# TopSide.net
KiCad netlist of a schematic drawn in Altium Designer
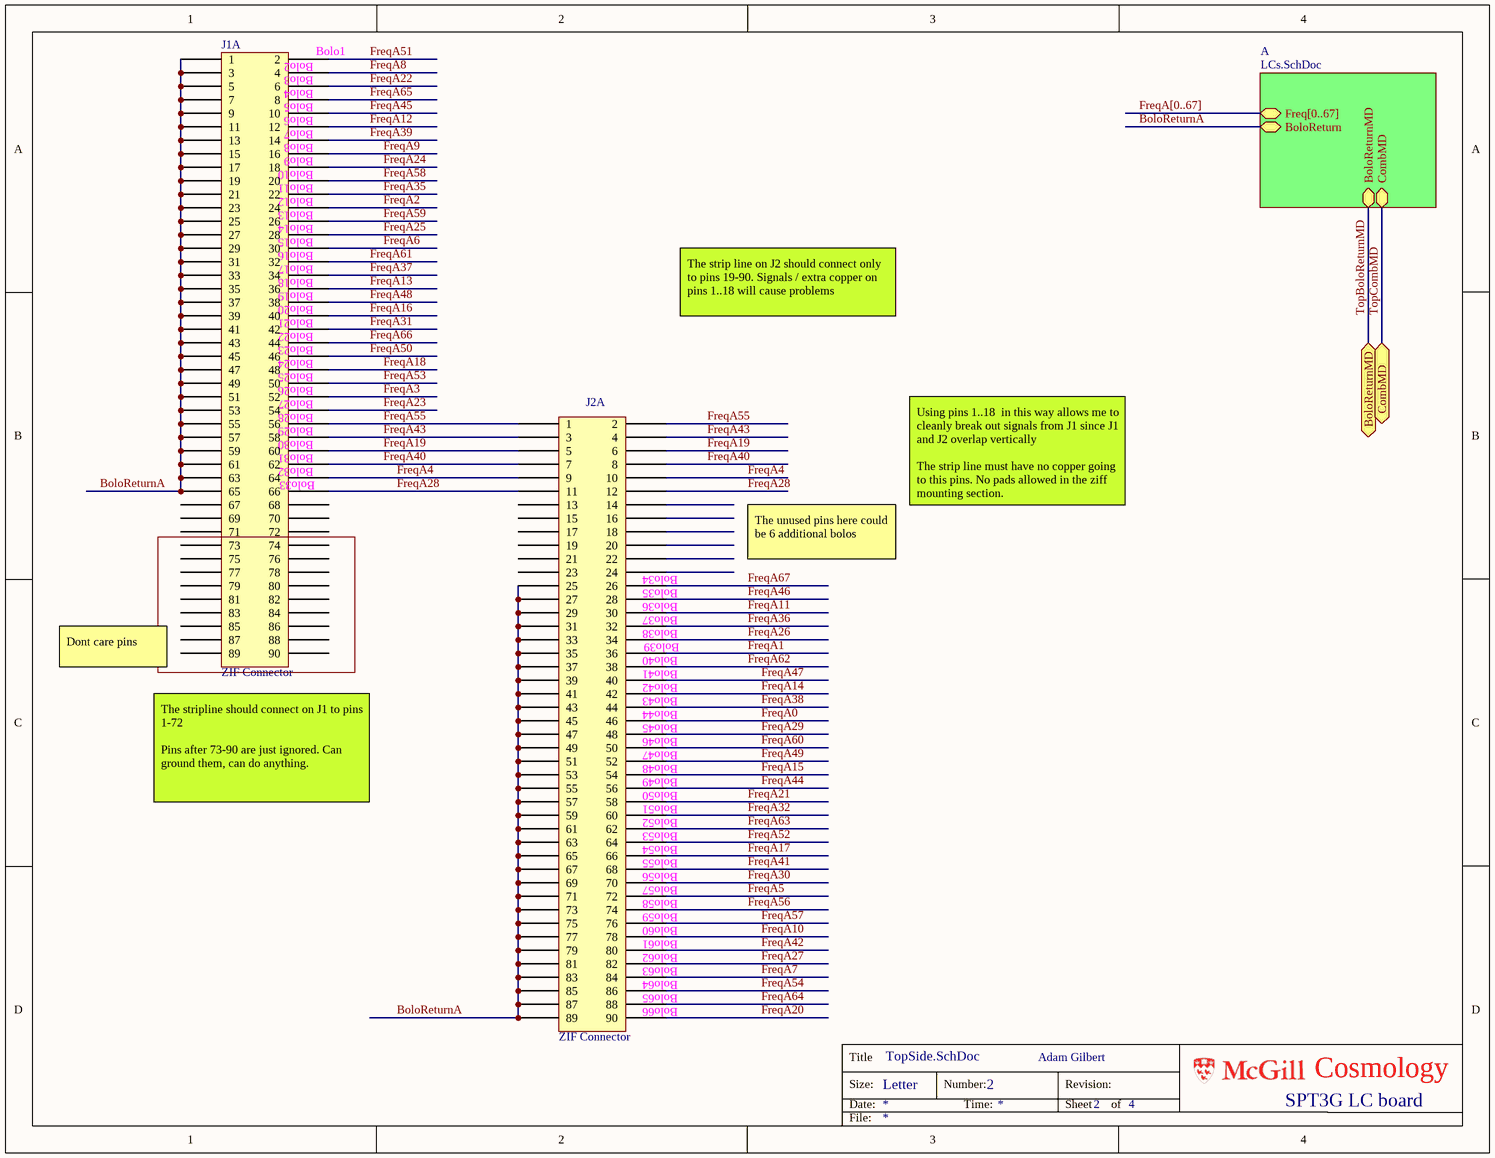
[diagram p0: TopSide.SchDoc]

(export (version "E")
  (design (tool "Eeschema 10.0.6"))
  (components
    (comp (ref "J1A")
      (value "ZIF Connector")
      (footprint "LCBoard_ZIFCon")
      (libsource (lib "SPT3G_LCBoard") (part "LCboard_FH16-90S-0.3SHW(05)"))
    )
    (comp (ref "J2A")
      (value "ZIF Connector")
      (footprint "LCBoard_ZIFCon")
      (libsource (lib "SPT3G_LCBoard") (part "LCboard_FH16-90S-0.3SHW(05)"))
    )
  )
  (nets
    (net (code "3") (name "/BoloReturnA") (class "Default")
      (node (ref "J1A") (pin "1") (pinfunction "1_1") (pintype "passive"))
      (node (ref "J1A") (pin "11") (pinfunction "11_11") (pintype "passive"))
      (node (ref "J1A") (pin "13") (pinfunction "13_13") (pintype "passive"))
      (node (ref "J1A") (pin "15") (pinfunction "15_15") (pintype "passive"))
      (node (ref "J1A") (pin "17") (pinfunction "17_17") (pintype "passive"))
      (node (ref "J1A") (pin "19") (pinfunction "19_19") (pintype "passive"))
      (node (ref "J1A") (pin "21") (pinfunction "21_21") (pintype "passive"))
      (node (ref "J1A") (pin "23") (pinfunction "23_23") (pintype "passive"))
      (node (ref "J1A") (pin "25") (pinfunction "25_25") (pintype "passive"))
      (node (ref "J1A") (pin "27") (pinfunction "27_27") (pintype "passive"))
      (node (ref "J1A") (pin "29") (pinfunction "29_29") (pintype "passive"))
      (node (ref "J1A") (pin "3") (pinfunction "3_3") (pintype "passive"))
      (node (ref "J1A") (pin "31") (pinfunction "31_31") (pintype "passive"))
      (node (ref "J1A") (pin "33") (pinfunction "33_33") (pintype "passive"))
      (node (ref "J1A") (pin "35") (pinfunction "35_35") (pintype "passive"))
      (node (ref "J1A") (pin "37") (pinfunction "37_37") (pintype "passive"))
      (node (ref "J1A") (pin "39") (pinfunction "39_39") (pintype "passive"))
      (node (ref "J1A") (pin "41") (pinfunction "41_41") (pintype "passive"))
      (node (ref "J1A") (pin "43") (pinfunction "43_43") (pintype "passive"))
      (node (ref "J1A") (pin "45") (pinfunction "45_45") (pintype "passive"))
      (node (ref "J1A") (pin "47") (pinfunction "47_47") (pintype "passive"))
      (node (ref "J1A") (pin "49") (pinfunction "49_49") (pintype "passive"))
      (node (ref "J1A") (pin "5") (pinfunction "5_5") (pintype "passive"))
      (node (ref "J1A") (pin "51") (pinfunction "51_51") (pintype "passive"))
      (node (ref "J1A") (pin "53") (pinfunction "53_53") (pintype "passive"))
      (node (ref "J1A") (pin "55") (pinfunction "55_55") (pintype "passive"))
      (node (ref "J1A") (pin "57") (pinfunction "57_57") (pintype "passive"))
      (node (ref "J1A") (pin "59") (pinfunction "59_59") (pintype "passive"))
      (node (ref "J1A") (pin "61") (pinfunction "61_61") (pintype "passive"))
      (node (ref "J1A") (pin "63") (pinfunction "63_63") (pintype "passive"))
      (node (ref "J1A") (pin "65") (pinfunction "65_65") (pintype "passive"))
      (node (ref "J1A") (pin "7") (pinfunction "7_7") (pintype "passive"))
      (node (ref "J1A") (pin "9") (pinfunction "9_9") (pintype "passive"))
      (node (ref "J2A") (pin "25") (pinfunction "25_25") (pintype "passive"))
      (node (ref "J2A") (pin "27") (pinfunction "27_27") (pintype "passive"))
      (node (ref "J2A") (pin "29") (pinfunction "29_29") (pintype "passive"))
      (node (ref "J2A") (pin "31") (pinfunction "31_31") (pintype "passive"))
      (node (ref "J2A") (pin "33") (pinfunction "33_33") (pintype "passive"))
      (node (ref "J2A") (pin "35") (pinfunction "35_35") (pintype "passive"))
      (node (ref "J2A") (pin "37") (pinfunction "37_37") (pintype "passive"))
      (node (ref "J2A") (pin "39") (pinfunction "39_39") (pintype "passive"))
      (node (ref "J2A") (pin "41") (pinfunction "41_41") (pintype "passive"))
      (node (ref "J2A") (pin "43") (pinfunction "43_43") (pintype "passive"))
      (node (ref "J2A") (pin "45") (pinfunction "45_45") (pintype "passive"))
      (node (ref "J2A") (pin "47") (pinfunction "47_47") (pintype "passive"))
      (node (ref "J2A") (pin "49") (pinfunction "49_49") (pintype "passive"))
      (node (ref "J2A") (pin "51") (pinfunction "51_51") (pintype "passive"))
      (node (ref "J2A") (pin "53") (pinfunction "53_53") (pintype "passive"))
      (node (ref "J2A") (pin "55") (pinfunction "55_55") (pintype "passive"))
      (node (ref "J2A") (pin "57") (pinfunction "57_57") (pintype "passive"))
      (node (ref "J2A") (pin "59") (pinfunction "59_59") (pintype "passive"))
      (node (ref "J2A") (pin "61") (pinfunction "61_61") (pintype "passive"))
      (node (ref "J2A") (pin "63") (pinfunction "63_63") (pintype "passive"))
      (node (ref "J2A") (pin "65") (pinfunction "65_65") (pintype "passive"))
      (node (ref "J2A") (pin "67") (pinfunction "67_67") (pintype "passive"))
      (node (ref "J2A") (pin "69") (pinfunction "69_69") (pintype "passive"))
      (node (ref "J2A") (pin "71") (pinfunction "71_71") (pintype "passive"))
      (node (ref "J2A") (pin "73") (pinfunction "73_73") (pintype "passive"))
      (node (ref "J2A") (pin "75") (pinfunction "75_75") (pintype "passive"))
      (node (ref "J2A") (pin "77") (pinfunction "77_77") (pintype "passive"))
      (node (ref "J2A") (pin "79") (pinfunction "79_79") (pintype "passive"))
      (node (ref "J2A") (pin "81") (pinfunction "81_81") (pintype "passive"))
      (node (ref "J2A") (pin "83") (pinfunction "83_83") (pintype "passive"))
      (node (ref "J2A") (pin "85") (pinfunction "85_85") (pintype "passive"))
      (node (ref "J2A") (pin "87") (pinfunction "87_87") (pintype "passive"))
      (node (ref "J2A") (pin "89") (pinfunction "89_89") (pintype "passive"))
    )
    (net (code "4") (name "/FreqA0") (class "Default")
      (node (ref "J2A") (pin "46") (pinfunction "46_46") (pintype "passive"))
    )
    (net (code "5") (name "/FreqA1") (class "Default")
      (node (ref "J2A") (pin "36") (pinfunction "36_36") (pintype "passive"))
    )
    (net (code "6") (name "/FreqA2") (class "Default")
      (node (ref "J1A") (pin "24") (pinfunction "24_24") (pintype "passive"))
    )
    (net (code "7") (name "/FreqA3") (class "Default")
      (node (ref "J1A") (pin "52") (pinfunction "52_52") (pintype "passive"))
    )
    (net (code "8") (name "/FreqA4") (class "Default")
      (node (ref "J1A") (pin "64") (pinfunction "64_64") (pintype "passive"))
      (node (ref "J2A") (pin "10") (pinfunction "10_10") (pintype "passive"))
      (node (ref "J2A") (pin "9") (pinfunction "9_9") (pintype "passive"))
    )
    (net (code "9") (name "/FreqA5") (class "Default")
      (node (ref "J2A") (pin "72") (pinfunction "72_72") (pintype "passive"))
    )
    (net (code "10") (name "/FreqA6") (class "Default")
      (node (ref "J1A") (pin "30") (pinfunction "30_30") (pintype "passive"))
    )
    (net (code "11") (name "/FreqA7") (class "Default")
      (node (ref "J2A") (pin "84") (pinfunction "84_84") (pintype "passive"))
    )
    (net (code "12") (name "/FreqA8") (class "Default")
      (node (ref "J1A") (pin "4") (pinfunction "4_4") (pintype "passive"))
    )
    (net (code "13") (name "/FreqA9") (class "Default")
      (node (ref "J1A") (pin "16") (pinfunction "16_16") (pintype "passive"))
    )
    (net (code "14") (name "/FreqA10") (class "Default")
      (node (ref "J2A") (pin "78") (pinfunction "78_78") (pintype "passive"))
    )
    (net (code "15") (name "/FreqA11") (class "Default")
      (node (ref "J2A") (pin "30") (pinfunction "30_30") (pintype "passive"))
    )
    (net (code "16") (name "/FreqA12") (class "Default")
      (node (ref "J1A") (pin "12") (pinfunction "12_12") (pintype "passive"))
    )
    (net (code "17") (name "/FreqA13") (class "Default")
      (node (ref "J1A") (pin "36") (pinfunction "36_36") (pintype "passive"))
    )
    (net (code "18") (name "/FreqA14") (class "Default")
      (node (ref "J2A") (pin "42") (pinfunction "42_42") (pintype "passive"))
    )
    (net (code "19") (name "/FreqA15") (class "Default")
      (node (ref "J2A") (pin "54") (pinfunction "54_54") (pintype "passive"))
    )
    (net (code "20") (name "/FreqA16") (class "Default")
      (node (ref "J1A") (pin "40") (pinfunction "40_40") (pintype "passive"))
    )
    (net (code "21") (name "/FreqA17") (class "Default")
      (node (ref "J2A") (pin "66") (pinfunction "66_66") (pintype "passive"))
    )
    (net (code "22") (name "/FreqA18") (class "Default")
      (node (ref "J1A") (pin "48") (pinfunction "48_48") (pintype "passive"))
    )
    (net (code "23") (name "/FreqA19") (class "Default")
      (node (ref "J1A") (pin "60") (pinfunction "60_60") (pintype "passive"))
      (node (ref "J2A") (pin "5") (pinfunction "5_5") (pintype "passive"))
      (node (ref "J2A") (pin "6") (pinfunction "6_6") (pintype "passive"))
    )
    (net (code "24") (name "/FreqA20") (class "Default")
      (node (ref "J2A") (pin "90") (pinfunction "90_90") (pintype "passive"))
    )
    (net (code "25") (name "/FreqA21") (class "Default")
      (node (ref "J2A") (pin "58") (pinfunction "58_58") (pintype "passive"))
    )
    (net (code "26") (name "/FreqA22") (class "Default")
      (node (ref "J1A") (pin "6") (pinfunction "6_6") (pintype "passive"))
    )
    (net (code "27") (name "/FreqA23") (class "Default")
      (node (ref "J1A") (pin "54") (pinfunction "54_54") (pintype "passive"))
    )
    (net (code "28") (name "/FreqA24") (class "Default")
      (node (ref "J1A") (pin "18") (pinfunction "18_18") (pintype "passive"))
    )
    (net (code "29") (name "/FreqA25") (class "Default")
      (node (ref "J1A") (pin "28") (pinfunction "28_28") (pintype "passive"))
    )
    (net (code "30") (name "/FreqA26") (class "Default")
      (node (ref "J2A") (pin "34") (pinfunction "34_34") (pintype "passive"))
    )
    (net (code "31") (name "/FreqA27") (class "Default")
      (node (ref "J2A") (pin "82") (pinfunction "82_82") (pintype "passive"))
    )
    (net (code "32") (name "/FreqA28") (class "Default")
      (node (ref "J1A") (pin "66") (pinfunction "66_66") (pintype "passive"))
      (node (ref "J2A") (pin "11") (pinfunction "11_11") (pintype "passive"))
      (node (ref "J2A") (pin "12") (pinfunction "12_12") (pintype "passive"))
    )
    (net (code "33") (name "/FreqA29") (class "Default")
      (node (ref "J2A") (pin "48") (pinfunction "48_48") (pintype "passive"))
    )
    (net (code "34") (name "/FreqA30") (class "Default")
      (node (ref "J2A") (pin "70") (pinfunction "70_70") (pintype "passive"))
    )
    (net (code "35") (name "/FreqA31") (class "Default")
      (node (ref "J1A") (pin "42") (pinfunction "42_42") (pintype "passive"))
    )
    (net (code "36") (name "/FreqA32") (class "Default")
      (node (ref "J2A") (pin "60") (pinfunction "60_60") (pintype "passive"))
    )
    (net (code "37") (name "/FreqA35") (class "Default")
      (node (ref "J1A") (pin "22") (pinfunction "22_22") (pintype "passive"))
    )
    (net (code "38") (name "/FreqA36") (class "Default")
      (node (ref "J2A") (pin "32") (pinfunction "32_32") (pintype "passive"))
    )
    (net (code "39") (name "/FreqA37") (class "Default")
      (node (ref "J1A") (pin "34") (pinfunction "34_34") (pintype "passive"))
    )
    (net (code "40") (name "/FreqA38") (class "Default")
      (node (ref "J2A") (pin "44") (pinfunction "44_44") (pintype "passive"))
    )
    (net (code "41") (name "/FreqA39") (class "Default")
      (node (ref "J1A") (pin "14") (pinfunction "14_14") (pintype "passive"))
    )
    (net (code "42") (name "/FreqA40") (class "Default")
      (node (ref "J1A") (pin "62") (pinfunction "62_62") (pintype "passive"))
      (node (ref "J2A") (pin "7") (pinfunction "7_7") (pintype "passive"))
      (node (ref "J2A") (pin "8") (pinfunction "8_8") (pintype "passive"))
    )
    (net (code "43") (name "/FreqA41") (class "Default")
      (node (ref "J2A") (pin "68") (pinfunction "68_68") (pintype "passive"))
    )
    (net (code "44") (name "/FreqA42") (class "Default")
      (node (ref "J2A") (pin "80") (pinfunction "80_80") (pintype "passive"))
    )
    (net (code "45") (name "/FreqA43") (class "Default")
      (node (ref "J1A") (pin "58") (pinfunction "58_58") (pintype "passive"))
      (node (ref "J2A") (pin "3") (pinfunction "3_3") (pintype "passive"))
      (node (ref "J2A") (pin "4") (pinfunction "4_4") (pintype "passive"))
    )
    (net (code "46") (name "/FreqA44") (class "Default")
      (node (ref "J2A") (pin "56") (pinfunction "56_56") (pintype "passive"))
    )
    (net (code "47") (name "/FreqA45") (class "Default")
      (node (ref "J1A") (pin "10") (pinfunction "10_10") (pintype "passive"))
    )
    (net (code "48") (name "/FreqA46") (class "Default")
      (node (ref "J2A") (pin "28") (pinfunction "28_28") (pintype "passive"))
    )
    (net (code "49") (name "/FreqA47") (class "Default")
      (node (ref "J2A") (pin "40") (pinfunction "40_40") (pintype "passive"))
    )
    (net (code "50") (name "/FreqA48") (class "Default")
      (node (ref "J1A") (pin "38") (pinfunction "38_38") (pintype "passive"))
    )
    (net (code "51") (name "/FreqA49") (class "Default")
      (node (ref "J2A") (pin "52") (pinfunction "52_52") (pintype "passive"))
    )
    (net (code "52") (name "/FreqA50") (class "Default")
      (node (ref "J1A") (pin "46") (pinfunction "46_46") (pintype "passive"))
    )
    (net (code "53") (name "/FreqA51") (class "Default")
      (node (ref "J1A") (pin "2") (pinfunction "2_2") (pintype "passive"))
    )
    (net (code "54") (name "/FreqA52") (class "Default")
      (node (ref "J2A") (pin "64") (pinfunction "64_64") (pintype "passive"))
    )
    (net (code "55") (name "/FreqA53") (class "Default")
      (node (ref "J1A") (pin "50") (pinfunction "50_50") (pintype "passive"))
    )
    (net (code "56") (name "/FreqA54") (class "Default")
      (node (ref "J2A") (pin "86") (pinfunction "86_86") (pintype "passive"))
    )
    (net (code "57") (name "/FreqA55") (class "Default")
      (node (ref "J1A") (pin "56") (pinfunction "56_56") (pintype "passive"))
      (node (ref "J2A") (pin "1") (pinfunction "1_1") (pintype "passive"))
      (node (ref "J2A") (pin "2") (pinfunction "2_2") (pintype "passive"))
    )
    (net (code "58") (name "/FreqA56") (class "Default")
      (node (ref "J2A") (pin "74") (pinfunction "74_74") (pintype "passive"))
    )
    (net (code "59") (name "/FreqA57") (class "Default")
      (node (ref "J2A") (pin "76") (pinfunction "76_76") (pintype "passive"))
    )
    (net (code "60") (name "/FreqA58") (class "Default")
      (node (ref "J1A") (pin "20") (pinfunction "20_20") (pintype "passive"))
    )
    (net (code "61") (name "/FreqA59") (class "Default")
      (node (ref "J1A") (pin "26") (pinfunction "26_26") (pintype "passive"))
    )
    (net (code "62") (name "/FreqA60") (class "Default")
      (node (ref "J2A") (pin "50") (pinfunction "50_50") (pintype "passive"))
    )
    (net (code "63") (name "/FreqA61") (class "Default")
      (node (ref "J1A") (pin "32") (pinfunction "32_32") (pintype "passive"))
    )
    (net (code "64") (name "/FreqA62") (class "Default")
      (node (ref "J2A") (pin "38") (pinfunction "38_38") (pintype "passive"))
    )
    (net (code "65") (name "/FreqA63") (class "Default")
      (node (ref "J2A") (pin "62") (pinfunction "62_62") (pintype "passive"))
    )
    (net (code "66") (name "/FreqA64") (class "Default")
      (node (ref "J2A") (pin "88") (pinfunction "88_88") (pintype "passive"))
    )
    (net (code "67") (name "/FreqA65") (class "Default")
      (node (ref "J1A") (pin "8") (pinfunction "8_8") (pintype "passive"))
    )
    (net (code "68") (name "/FreqA66") (class "Default")
      (node (ref "J1A") (pin "44") (pinfunction "44_44") (pintype "passive"))
    )
    (net (code "69") (name "/FreqA67") (class "Default")
      (node (ref "J2A") (pin "26") (pinfunction "26_26") (pintype "passive"))
    )
    (net (code "73") (name "unconnected-(J1A-Pad67)") (class "Default")
      (node (ref "J1A") (pin "67") (pinfunction "67_67") (pintype "passive"))
    )
    (net (code "74") (name "unconnected-(J1A-Pad68)") (class "Default")
      (node (ref "J1A") (pin "68") (pinfunction "68_68") (pintype "passive"))
    )
    (net (code "75") (name "unconnected-(J1A-Pad69)") (class "Default")
      (node (ref "J1A") (pin "69") (pinfunction "69_69") (pintype "passive"))
    )
    (net (code "76") (name "unconnected-(J1A-Pad70)") (class "Default")
      (node (ref "J1A") (pin "70") (pinfunction "70_70") (pintype "passive"))
    )
    (net (code "77") (name "unconnected-(J1A-Pad71)") (class "Default")
      (node (ref "J1A") (pin "71") (pinfunction "71_71") (pintype "passive"))
    )
    (net (code "78") (name "unconnected-(J1A-Pad72)") (class "Default")
      (node (ref "J1A") (pin "72") (pinfunction "72_72") (pintype "passive"))
    )
    (net (code "79") (name "unconnected-(J1A-Pad73)") (class "Default")
      (node (ref "J1A") (pin "73") (pinfunction "73_73") (pintype "passive"))
    )
    (net (code "80") (name "unconnected-(J1A-Pad74)") (class "Default")
      (node (ref "J1A") (pin "74") (pinfunction "74_74") (pintype "passive"))
    )
    (net (code "81") (name "unconnected-(J1A-Pad75)") (class "Default")
      (node (ref "J1A") (pin "75") (pinfunction "75_75") (pintype "passive"))
    )
    (net (code "82") (name "unconnected-(J1A-Pad76)") (class "Default")
      (node (ref "J1A") (pin "76") (pinfunction "76_76") (pintype "passive"))
    )
    (net (code "83") (name "unconnected-(J1A-Pad77)") (class "Default")
      (node (ref "J1A") (pin "77") (pinfunction "77_77") (pintype "passive"))
    )
    (net (code "84") (name "unconnected-(J1A-Pad78)") (class "Default")
      (node (ref "J1A") (pin "78") (pinfunction "78_78") (pintype "passive"))
    )
    (net (code "85") (name "unconnected-(J1A-Pad79)") (class "Default")
      (node (ref "J1A") (pin "79") (pinfunction "79_79") (pintype "passive"))
    )
    (net (code "86") (name "unconnected-(J1A-Pad80)") (class "Default")
      (node (ref "J1A") (pin "80") (pinfunction "80_80") (pintype "passive"))
    )
    (net (code "87") (name "unconnected-(J1A-Pad81)") (class "Default")
      (node (ref "J1A") (pin "81") (pinfunction "81_81") (pintype "passive"))
    )
    (net (code "88") (name "unconnected-(J1A-Pad82)") (class "Default")
      (node (ref "J1A") (pin "82") (pinfunction "82_82") (pintype "passive"))
    )
    (net (code "89") (name "unconnected-(J1A-Pad83)") (class "Default")
      (node (ref "J1A") (pin "83") (pinfunction "83_83") (pintype "passive"))
    )
    (net (code "90") (name "unconnected-(J1A-Pad84)") (class "Default")
      (node (ref "J1A") (pin "84") (pinfunction "84_84") (pintype "passive"))
    )
    (net (code "91") (name "unconnected-(J1A-Pad85)") (class "Default")
      (node (ref "J1A") (pin "85") (pinfunction "85_85") (pintype "passive"))
    )
    (net (code "92") (name "unconnected-(J1A-Pad86)") (class "Default")
      (node (ref "J1A") (pin "86") (pinfunction "86_86") (pintype "passive"))
    )
    (net (code "93") (name "unconnected-(J1A-Pad87)") (class "Default")
      (node (ref "J1A") (pin "87") (pinfunction "87_87") (pintype "passive"))
    )
    (net (code "94") (name "unconnected-(J1A-Pad88)") (class "Default")
      (node (ref "J1A") (pin "88") (pinfunction "88_88") (pintype "passive"))
    )
    (net (code "95") (name "unconnected-(J1A-Pad89)") (class "Default")
      (node (ref "J1A") (pin "89") (pinfunction "89_89") (pintype "passive"))
    )
    (net (code "96") (name "unconnected-(J1A-Pad90)") (class "Default")
      (node (ref "J1A") (pin "90") (pinfunction "90_90") (pintype "passive"))
    )
    (net (code "97") (name "unconnected-(J2A-Pad13)") (class "Default")
      (node (ref "J2A") (pin "13") (pinfunction "13_13") (pintype "passive"))
    )
    (net (code "98") (name "unconnected-(J2A-Pad14)") (class "Default")
      (node (ref "J2A") (pin "14") (pinfunction "14_14") (pintype "passive"))
    )
    (net (code "99") (name "unconnected-(J2A-Pad15)") (class "Default")
      (node (ref "J2A") (pin "15") (pinfunction "15_15") (pintype "passive"))
    )
    (net (code "100") (name "unconnected-(J2A-Pad16)") (class "Default")
      (node (ref "J2A") (pin "16") (pinfunction "16_16") (pintype "passive"))
    )
    (net (code "101") (name "unconnected-(J2A-Pad17)") (class "Default")
      (node (ref "J2A") (pin "17") (pinfunction "17_17") (pintype "passive"))
    )
    (net (code "102") (name "unconnected-(J2A-Pad18)") (class "Default")
      (node (ref "J2A") (pin "18") (pinfunction "18_18") (pintype "passive"))
    )
    (net (code "103") (name "unconnected-(J2A-Pad19)") (class "Default")
      (node (ref "J2A") (pin "19") (pinfunction "19_19") (pintype "passive"))
    )
    (net (code "104") (name "unconnected-(J2A-Pad20)") (class "Default")
      (node (ref "J2A") (pin "20") (pinfunction "20_20") (pintype "passive"))
    )
    (net (code "105") (name "unconnected-(J2A-Pad21)") (class "Default")
      (node (ref "J2A") (pin "21") (pinfunction "21_21") (pintype "passive"))
    )
    (net (code "106") (name "unconnected-(J2A-Pad22)") (class "Default")
      (node (ref "J2A") (pin "22") (pinfunction "22_22") (pintype "passive"))
    )
    (net (code "107") (name "unconnected-(J2A-Pad23)") (class "Default")
      (node (ref "J2A") (pin "23") (pinfunction "23_23") (pintype "passive"))
    )
    (net (code "108") (name "unconnected-(J2A-Pad24)") (class "Default")
      (node (ref "J2A") (pin "24") (pinfunction "24_24") (pintype "passive"))
    )
  )
)
